# subliminal1.net
KiCad netlist of a schematic drawn in EAGLE
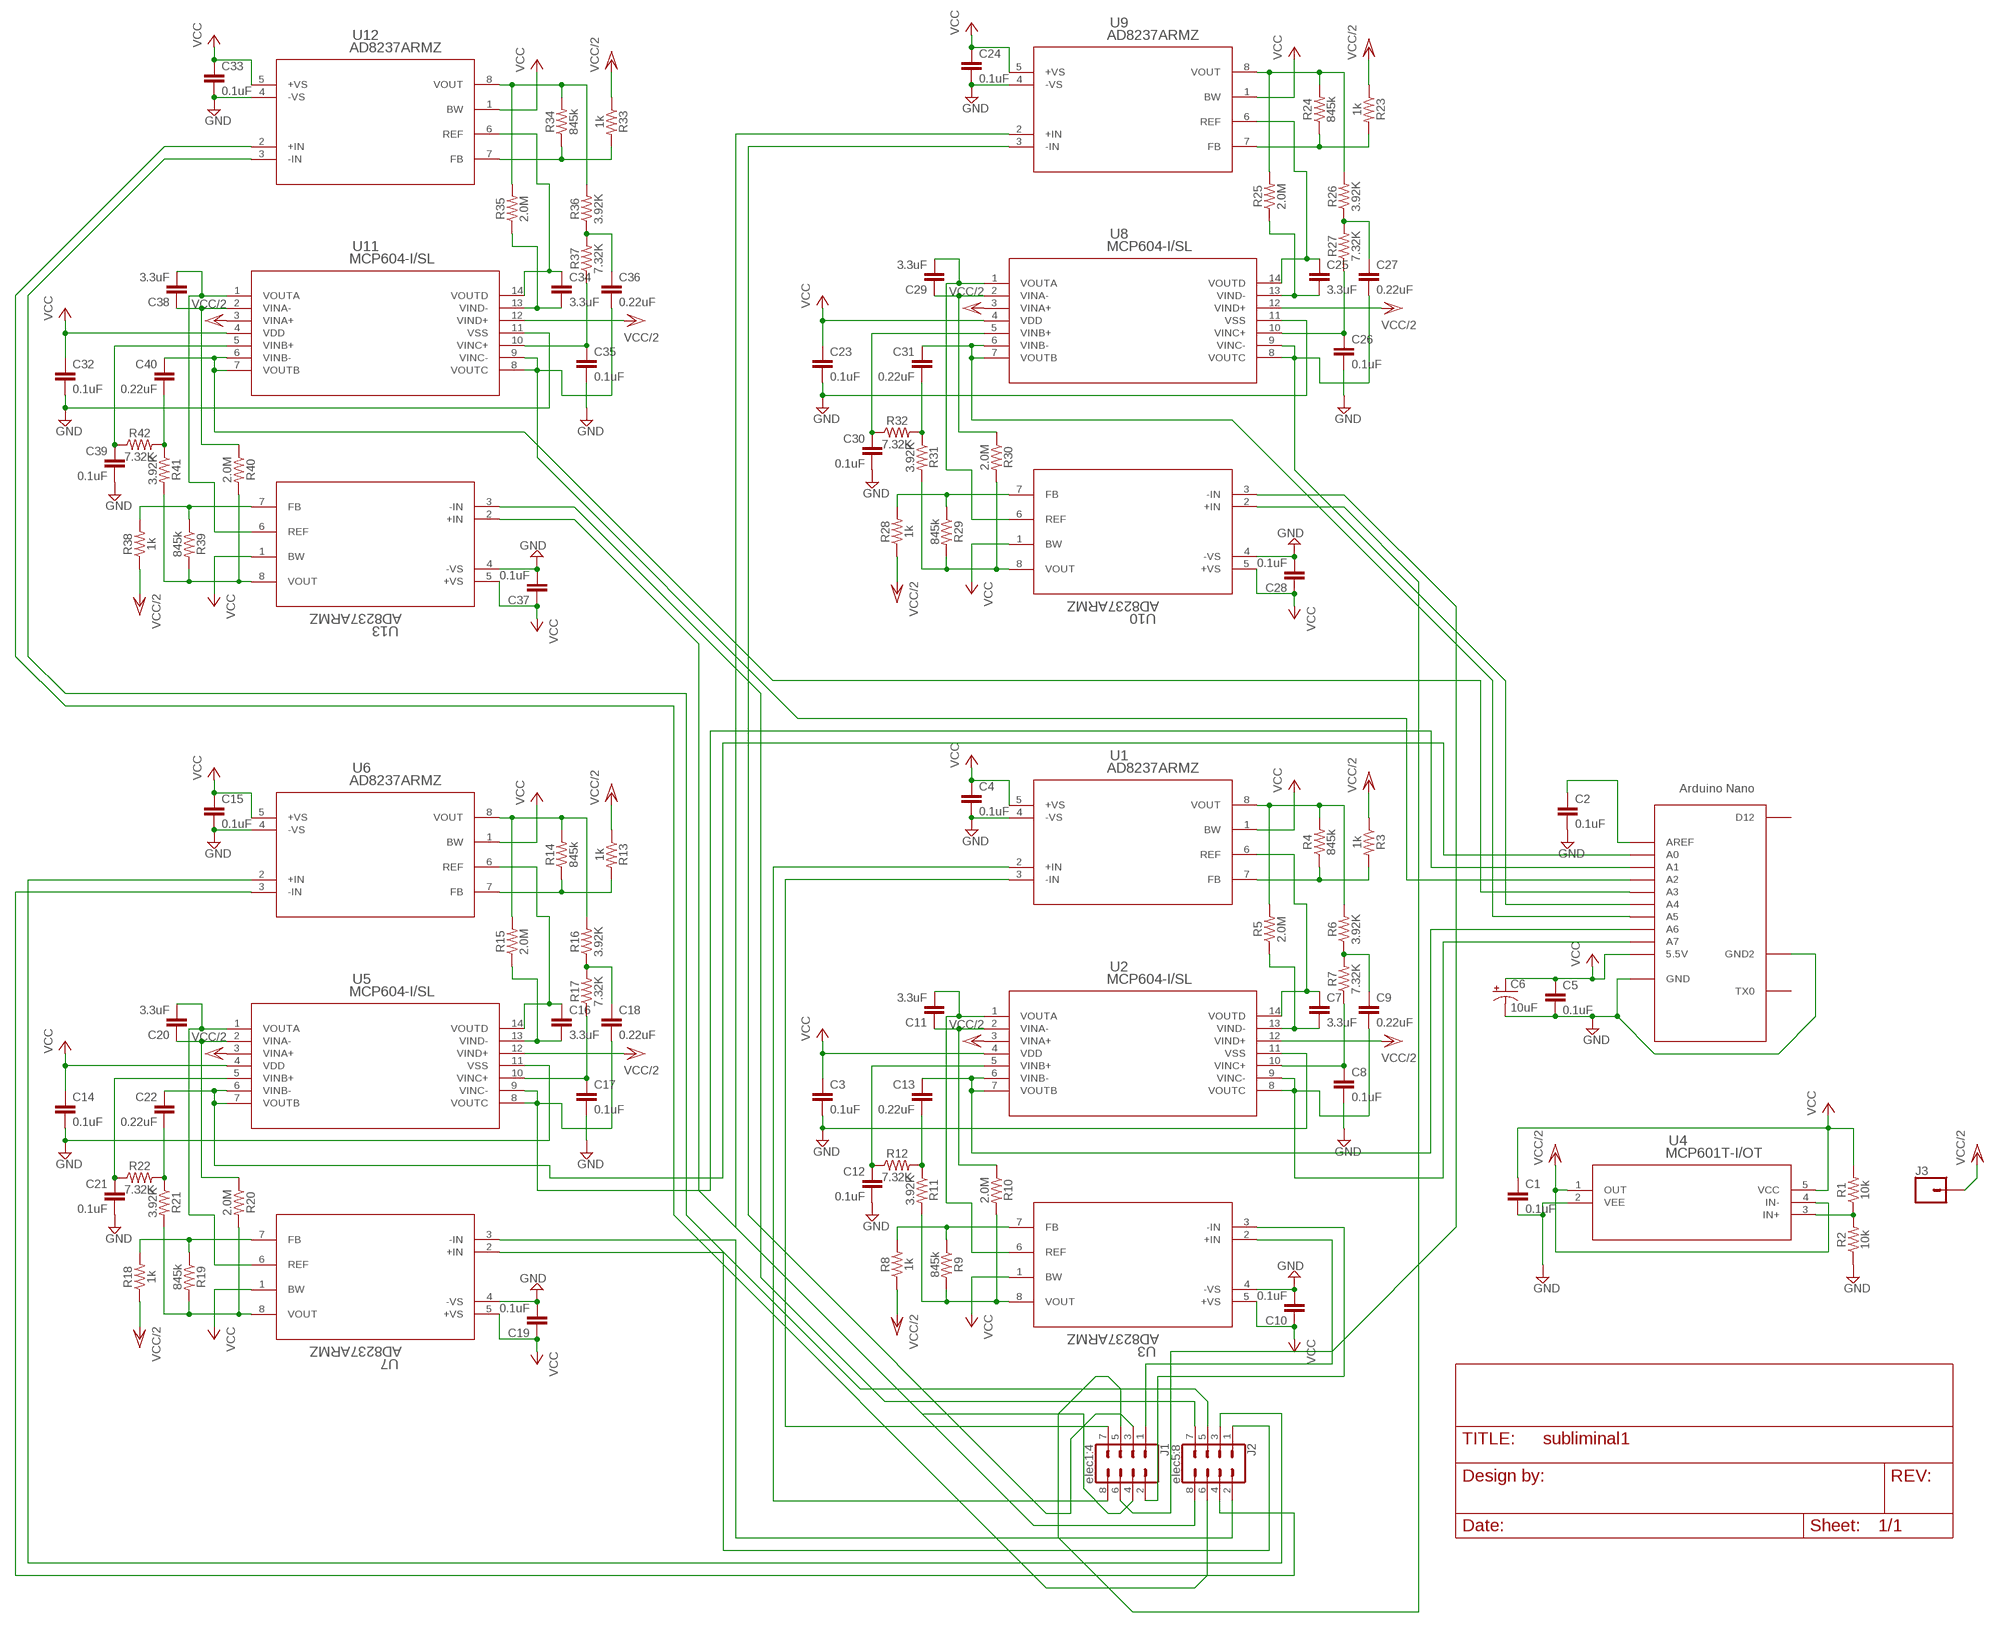
[diagram p0: schematic, sheet 1, part 1 of 2]
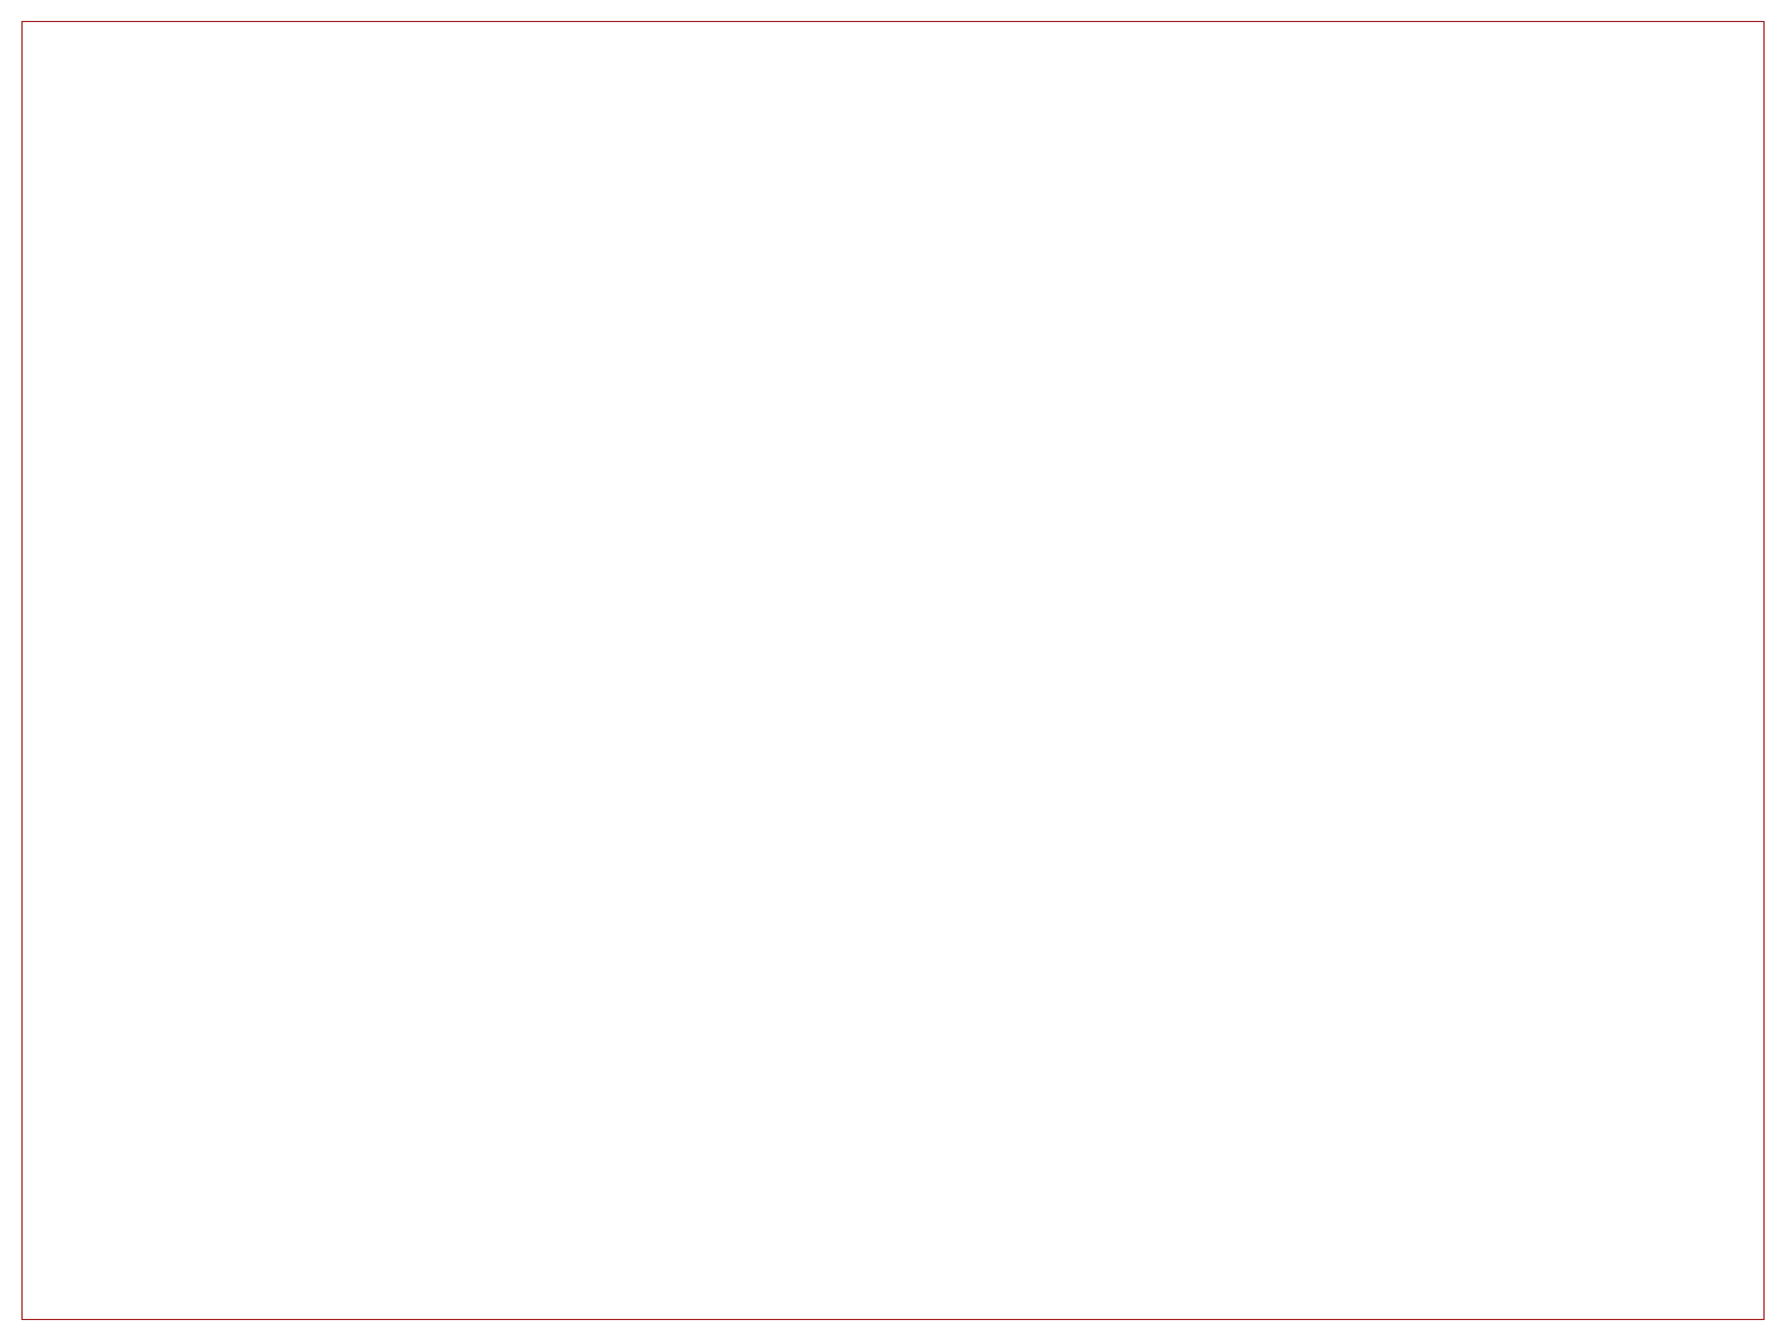
[diagram p1: schematic, sheet 1, part 2 of 2]

(export (version "E")
  (design (tool "Eeschema 10.0.6"))
  (components
    (comp (ref "C1")
      (value "0.1uF")
      (footprint "eagle-import:0603")
      (libsource (lib "eagle-import") (part "0.1UF-0603-25V-(+80/-20%)"))
    )
    (comp (ref "C2")
      (value "0.1uF")
      (footprint "eagle-import:0603")
      (libsource (lib "eagle-import") (part "0.1UF-0603-25V-(+80/-20%)"))
    )
    (comp (ref "C3")
      (value "0.1uF")
      (footprint "eagle-import:0603")
      (libsource (lib "eagle-import") (part "0.1UF-0603-25V-(+80/-20%)"))
    )
    (comp (ref "C4")
      (value "0.1uF")
      (footprint "eagle-import:0603")
      (libsource (lib "eagle-import") (part "0.1UF-0603-25V-(+80/-20%)"))
    )
    (comp (ref "C5")
      (value "0.1uF")
      (footprint "eagle-import:0603")
      (libsource (lib "eagle-import") (part "0.1UF-0603-25V-(+80/-20%)"))
    )
    (comp (ref "C6")
      (value "10uF")
      (footprint "eagle-import:EIA3216")
      (libsource (lib "eagle-import") (part "10UF-POLAR-EIA3216-16V-10%(TANT)"))
    )
    (comp (ref "C7")
      (value "3.3uF")
      (footprint "eagle-import:0603")
      (libsource (lib "eagle-import") (part "3.3UF-0603-10V-10%"))
    )
    (comp (ref "C8")
      (value "0.1uF")
      (footprint "eagle-import:0603")
      (libsource (lib "eagle-import") (part "0.1UF-0603-25V-(+80/-20%)"))
    )
    (comp (ref "C9")
      (value "0.22uF")
      (footprint "eagle-import:0603")
      (libsource (lib "eagle-import") (part "0.22UF-0603-25V-10%"))
    )
    (comp (ref "C10")
      (value "0.1uF")
      (footprint "eagle-import:0603")
      (libsource (lib "eagle-import") (part "0.1UF-0603-25V-(+80/-20%)"))
    )
    (comp (ref "C11")
      (value "3.3uF")
      (footprint "eagle-import:0603")
      (libsource (lib "eagle-import") (part "3.3UF-0603-10V-10%"))
    )
    (comp (ref "C12")
      (value "0.1uF")
      (footprint "eagle-import:0603")
      (libsource (lib "eagle-import") (part "0.1UF-0603-25V-(+80/-20%)"))
    )
    (comp (ref "C13")
      (value "0.22uF")
      (footprint "eagle-import:0603")
      (libsource (lib "eagle-import") (part "0.22UF-0603-25V-10%"))
    )
    (comp (ref "C14")
      (value "0.1uF")
      (footprint "eagle-import:0603")
      (libsource (lib "eagle-import") (part "0.1UF-0603-25V-(+80/-20%)"))
    )
    (comp (ref "C15")
      (value "0.1uF")
      (footprint "eagle-import:0603")
      (libsource (lib "eagle-import") (part "0.1UF-0603-25V-(+80/-20%)"))
    )
    (comp (ref "C16")
      (value "3.3uF")
      (footprint "eagle-import:0603")
      (libsource (lib "eagle-import") (part "3.3UF-0603-10V-10%"))
    )
    (comp (ref "C17")
      (value "0.1uF")
      (footprint "eagle-import:0603")
      (libsource (lib "eagle-import") (part "0.1UF-0603-25V-(+80/-20%)"))
    )
    (comp (ref "C18")
      (value "0.22uF")
      (footprint "eagle-import:0603")
      (libsource (lib "eagle-import") (part "0.22UF-0603-25V-10%"))
    )
    (comp (ref "C19")
      (value "0.1uF")
      (footprint "eagle-import:0603")
      (libsource (lib "eagle-import") (part "0.1UF-0603-25V-(+80/-20%)"))
    )
    (comp (ref "C20")
      (value "3.3uF")
      (footprint "eagle-import:0603")
      (libsource (lib "eagle-import") (part "3.3UF-0603-10V-10%"))
    )
    (comp (ref "C21")
      (value "0.1uF")
      (footprint "eagle-import:0603")
      (libsource (lib "eagle-import") (part "0.1UF-0603-25V-(+80/-20%)"))
    )
    (comp (ref "C22")
      (value "0.22uF")
      (footprint "eagle-import:0603")
      (libsource (lib "eagle-import") (part "0.22UF-0603-25V-10%"))
    )
    (comp (ref "C23")
      (value "0.1uF")
      (footprint "eagle-import:0603")
      (libsource (lib "eagle-import") (part "0.1UF-0603-25V-(+80/-20%)"))
    )
    (comp (ref "C24")
      (value "0.1uF")
      (footprint "eagle-import:0603")
      (libsource (lib "eagle-import") (part "0.1UF-0603-25V-(+80/-20%)"))
    )
    (comp (ref "C25")
      (value "3.3uF")
      (footprint "eagle-import:0603")
      (libsource (lib "eagle-import") (part "3.3UF-0603-10V-10%"))
    )
    (comp (ref "C26")
      (value "0.1uF")
      (footprint "eagle-import:0603")
      (libsource (lib "eagle-import") (part "0.1UF-0603-25V-(+80/-20%)"))
    )
    (comp (ref "C27")
      (value "0.22uF")
      (footprint "eagle-import:0603")
      (libsource (lib "eagle-import") (part "0.22UF-0603-25V-10%"))
    )
    (comp (ref "C28")
      (value "0.1uF")
      (footprint "eagle-import:0603")
      (libsource (lib "eagle-import") (part "0.1UF-0603-25V-(+80/-20%)"))
    )
    (comp (ref "C29")
      (value "3.3uF")
      (footprint "eagle-import:0603")
      (libsource (lib "eagle-import") (part "3.3UF-0603-10V-10%"))
    )
    (comp (ref "C30")
      (value "0.1uF")
      (footprint "eagle-import:0603")
      (libsource (lib "eagle-import") (part "0.1UF-0603-25V-(+80/-20%)"))
    )
    (comp (ref "C31")
      (value "0.22uF")
      (footprint "eagle-import:0603")
      (libsource (lib "eagle-import") (part "0.22UF-0603-25V-10%"))
    )
    (comp (ref "C32")
      (value "0.1uF")
      (footprint "eagle-import:0603")
      (libsource (lib "eagle-import") (part "0.1UF-0603-25V-(+80/-20%)"))
    )
    (comp (ref "C33")
      (value "0.1uF")
      (footprint "eagle-import:0603")
      (libsource (lib "eagle-import") (part "0.1UF-0603-25V-(+80/-20%)"))
    )
    (comp (ref "C34")
      (value "3.3uF")
      (footprint "eagle-import:0603")
      (libsource (lib "eagle-import") (part "3.3UF-0603-10V-10%"))
    )
    (comp (ref "C35")
      (value "0.1uF")
      (footprint "eagle-import:0603")
      (libsource (lib "eagle-import") (part "0.1UF-0603-25V-(+80/-20%)"))
    )
    (comp (ref "C36")
      (value "0.22uF")
      (footprint "eagle-import:0603")
      (libsource (lib "eagle-import") (part "0.22UF-0603-25V-10%"))
    )
    (comp (ref "C37")
      (value "0.1uF")
      (footprint "eagle-import:0603")
      (libsource (lib "eagle-import") (part "0.1UF-0603-25V-(+80/-20%)"))
    )
    (comp (ref "C38")
      (value "3.3uF")
      (footprint "eagle-import:0603")
      (libsource (lib "eagle-import") (part "3.3UF-0603-10V-10%"))
    )
    (comp (ref "C39")
      (value "0.1uF")
      (footprint "eagle-import:0603")
      (libsource (lib "eagle-import") (part "0.1UF-0603-25V-(+80/-20%)"))
    )
    (comp (ref "C40")
      (value "0.22uF")
      (footprint "eagle-import:0603")
      (libsource (lib "eagle-import") (part "0.22UF-0603-25V-10%"))
    )
    (comp (ref "J1")
      (value "elec1:4")
      (footprint "eagle-import:2X4")
      (libsource (lib "eagle-import") (part "CONN_04X2"))
    )
    (comp (ref "J2")
      (value "elec5:8")
      (footprint "eagle-import:2X4")
      (libsource (lib "eagle-import") (part "CONN_04X2"))
    )
    (comp (ref "J3")
      (value "CONN_01")
      (footprint "eagle-import:1X01")
      (libsource (lib "eagle-import") (part "CONN_01"))
    )
    (comp (ref "R1")
      (value "10k")
      (footprint "eagle-import:0603")
      (libsource (lib "eagle-import") (part "10KOHM-0603-1/10W-1%"))
    )
    (comp (ref "R2")
      (value "10k")
      (footprint "eagle-import:0603")
      (libsource (lib "eagle-import") (part "10KOHM-0603-1/10W-1%"))
    )
    (comp (ref "R3")
      (value "1k")
      (footprint "eagle-import:0603")
      (libsource (lib "eagle-import") (part "1KOHM-0603-1/10W-1%"))
    )
    (comp (ref "R4")
      (value "845k")
      (footprint "eagle-import:0603")
      (libsource (lib "eagle-import") (part "845KOHM-0603-1/10W-1%"))
    )
    (comp (ref "R5")
      (value "2.0M")
      (footprint "eagle-import:0603")
      (libsource (lib "eagle-import") (part "2MOHMS-0603-1/10W-1%"))
    )
    (comp (ref "R6")
      (value "3.92K")
      (footprint "eagle-import:0603")
      (libsource (lib "eagle-import") (part "3.92KOHM-0603-1/10W-1%"))
    )
    (comp (ref "R7")
      (value "7.32K")
      (footprint "eagle-import:0603")
      (libsource (lib "eagle-import") (part "7.32KOHM-0603-1/10W-1%"))
    )
    (comp (ref "R8")
      (value "1k")
      (footprint "eagle-import:0603")
      (libsource (lib "eagle-import") (part "1KOHM-0603-1/10W-1%"))
    )
    (comp (ref "R9")
      (value "845k")
      (footprint "eagle-import:0603")
      (libsource (lib "eagle-import") (part "845KOHM-0603-1/10W-1%"))
    )
    (comp (ref "R10")
      (value "2.0M")
      (footprint "eagle-import:0603")
      (libsource (lib "eagle-import") (part "2MOHMS-0603-1/10W-1%"))
    )
    (comp (ref "R11")
      (value "3.92K")
      (footprint "eagle-import:0603")
      (libsource (lib "eagle-import") (part "3.92KOHM-0603-1/10W-1%"))
    )
    (comp (ref "R12")
      (value "7.32K")
      (footprint "eagle-import:0603")
      (libsource (lib "eagle-import") (part "7.32KOHM-0603-1/10W-1%"))
    )
    (comp (ref "R13")
      (value "1k")
      (footprint "eagle-import:0603")
      (libsource (lib "eagle-import") (part "1KOHM-0603-1/10W-1%"))
    )
    (comp (ref "R14")
      (value "845k")
      (footprint "eagle-import:0603")
      (libsource (lib "eagle-import") (part "845KOHM-0603-1/10W-1%"))
    )
    (comp (ref "R15")
      (value "2.0M")
      (footprint "eagle-import:0603")
      (libsource (lib "eagle-import") (part "2MOHMS-0603-1/10W-1%"))
    )
    (comp (ref "R16")
      (value "3.92K")
      (footprint "eagle-import:0603")
      (libsource (lib "eagle-import") (part "3.92KOHM-0603-1/10W-1%"))
    )
    (comp (ref "R17")
      (value "7.32K")
      (footprint "eagle-import:0603")
      (libsource (lib "eagle-import") (part "7.32KOHM-0603-1/10W-1%"))
    )
    (comp (ref "R18")
      (value "1k")
      (footprint "eagle-import:0603")
      (libsource (lib "eagle-import") (part "1KOHM-0603-1/10W-1%"))
    )
    (comp (ref "R19")
      (value "845k")
      (footprint "eagle-import:0603")
      (libsource (lib "eagle-import") (part "845KOHM-0603-1/10W-1%"))
    )
    (comp (ref "R20")
      (value "2.0M")
      (footprint "eagle-import:0603")
      (libsource (lib "eagle-import") (part "2MOHMS-0603-1/10W-1%"))
    )
    (comp (ref "R21")
      (value "3.92K")
      (footprint "eagle-import:0603")
      (libsource (lib "eagle-import") (part "3.92KOHM-0603-1/10W-1%"))
    )
    (comp (ref "R22")
      (value "7.32K")
      (footprint "eagle-import:0603")
      (libsource (lib "eagle-import") (part "7.32KOHM-0603-1/10W-1%"))
    )
    (comp (ref "R23")
      (value "1k")
      (footprint "eagle-import:0603")
      (libsource (lib "eagle-import") (part "1KOHM-0603-1/10W-1%"))
    )
    (comp (ref "R24")
      (value "845k")
      (footprint "eagle-import:0603")
      (libsource (lib "eagle-import") (part "845KOHM-0603-1/10W-1%"))
    )
    (comp (ref "R25")
      (value "2.0M")
      (footprint "eagle-import:0603")
      (libsource (lib "eagle-import") (part "2MOHMS-0603-1/10W-1%"))
    )
    (comp (ref "R26")
      (value "3.92K")
      (footprint "eagle-import:0603")
      (libsource (lib "eagle-import") (part "3.92KOHM-0603-1/10W-1%"))
    )
    (comp (ref "R27")
      (value "7.32K")
      (footprint "eagle-import:0603")
      (libsource (lib "eagle-import") (part "7.32KOHM-0603-1/10W-1%"))
    )
    (comp (ref "R28")
      (value "1k")
      (footprint "eagle-import:0603")
      (libsource (lib "eagle-import") (part "1KOHM-0603-1/10W-1%"))
    )
    (comp (ref "R29")
      (value "845k")
      (footprint "eagle-import:0603")
      (libsource (lib "eagle-import") (part "845KOHM-0603-1/10W-1%"))
    )
    (comp (ref "R30")
      (value "2.0M")
      (footprint "eagle-import:0603")
      (libsource (lib "eagle-import") (part "2MOHMS-0603-1/10W-1%"))
    )
    (comp (ref "R31")
      (value "3.92K")
      (footprint "eagle-import:0603")
      (libsource (lib "eagle-import") (part "3.92KOHM-0603-1/10W-1%"))
    )
    (comp (ref "R32")
      (value "7.32K")
      (footprint "eagle-import:0603")
      (libsource (lib "eagle-import") (part "7.32KOHM-0603-1/10W-1%"))
    )
    (comp (ref "R33")
      (value "1k")
      (footprint "eagle-import:0603")
      (libsource (lib "eagle-import") (part "1KOHM-0603-1/10W-1%"))
    )
    (comp (ref "R34")
      (value "845k")
      (footprint "eagle-import:0603")
      (libsource (lib "eagle-import") (part "845KOHM-0603-1/10W-1%"))
    )
    (comp (ref "R35")
      (value "2.0M")
      (footprint "eagle-import:0603")
      (libsource (lib "eagle-import") (part "2MOHMS-0603-1/10W-1%"))
    )
    (comp (ref "R36")
      (value "3.92K")
      (footprint "eagle-import:0603")
      (libsource (lib "eagle-import") (part "3.92KOHM-0603-1/10W-1%"))
    )
    (comp (ref "R37")
      (value "7.32K")
      (footprint "eagle-import:0603")
      (libsource (lib "eagle-import") (part "7.32KOHM-0603-1/10W-1%"))
    )
    (comp (ref "R38")
      (value "1k")
      (footprint "eagle-import:0603")
      (libsource (lib "eagle-import") (part "1KOHM-0603-1/10W-1%"))
    )
    (comp (ref "R39")
      (value "845k")
      (footprint "eagle-import:0603")
      (libsource (lib "eagle-import") (part "845KOHM-0603-1/10W-1%"))
    )
    (comp (ref "R40")
      (value "2.0M")
      (footprint "eagle-import:0603")
      (libsource (lib "eagle-import") (part "2MOHMS-0603-1/10W-1%"))
    )
    (comp (ref "R41")
      (value "3.92K")
      (footprint "eagle-import:0603")
      (libsource (lib "eagle-import") (part "3.92KOHM-0603-1/10W-1%"))
    )
    (comp (ref "R42")
      (value "7.32K")
      (footprint "eagle-import:0603")
      (libsource (lib "eagle-import") (part "7.32KOHM-0603-1/10W-1%"))
    )
    (comp (ref "U$1")
      (value "ANALOG-NANO")
      (footprint "eagle-import:ANANANOMIN")
      (libsource (lib "eagle-import") (part "ANALOG-NANO"))
    )
    (comp (ref "U1")
      (value "AD8237ARMZ")
      (footprint "eagle-import:RM_8")
      (libsource (lib "eagle-import") (part "AD8237ARMZ"))
    )
    (comp (ref "U2")
      (value "MCP604-I/SL")
      (footprint "eagle-import:SOIC14-N_MC")
      (fields (field (name "MANUFACTURER_PART_NUMBER") "MCP604ISL"))
      (libsource (lib "eagle-import") (part "MCP604-I/SL"))
    )
    (comp (ref "U3")
      (value "AD8237ARMZ")
      (footprint "eagle-import:RM_8")
      (libsource (lib "eagle-import") (part "AD8237ARMZ"))
    )
    (comp (ref "U4")
      (value "MCP601T-I/OT")
      (footprint "eagle-import:SOT-23-5_MC")
      (fields (field (name "MANUFACTURER_PART_NUMBER") "MCP601TIOT"))
      (libsource (lib "eagle-import") (part "MCP601T-I/OT"))
    )
    (comp (ref "U5")
      (value "MCP604-I/SL")
      (footprint "eagle-import:SOIC14-N_MC")
      (fields (field (name "MANUFACTURER_PART_NUMBER") "MCP604ISL"))
      (libsource (lib "eagle-import") (part "MCP604-I/SL"))
    )
    (comp (ref "U6")
      (value "AD8237ARMZ")
      (footprint "eagle-import:RM_8")
      (libsource (lib "eagle-import") (part "AD8237ARMZ"))
    )
    (comp (ref "U7")
      (value "AD8237ARMZ")
      (footprint "eagle-import:RM_8")
      (libsource (lib "eagle-import") (part "AD8237ARMZ"))
    )
    (comp (ref "U8")
      (value "MCP604-I/SL")
      (footprint "eagle-import:SOIC14-N_MC")
      (fields (field (name "MANUFACTURER_PART_NUMBER") "MCP604ISL"))
      (libsource (lib "eagle-import") (part "MCP604-I/SL"))
    )
    (comp (ref "U9")
      (value "AD8237ARMZ")
      (footprint "eagle-import:RM_8")
      (libsource (lib "eagle-import") (part "AD8237ARMZ"))
    )
    (comp (ref "U10")
      (value "AD8237ARMZ")
      (footprint "eagle-import:RM_8")
      (libsource (lib "eagle-import") (part "AD8237ARMZ"))
    )
    (comp (ref "U11")
      (value "MCP604-I/SL")
      (footprint "eagle-import:SOIC14-N_MC")
      (fields (field (name "MANUFACTURER_PART_NUMBER") "MCP604ISL"))
      (libsource (lib "eagle-import") (part "MCP604-I/SL"))
    )
    (comp (ref "U12")
      (value "AD8237ARMZ")
      (footprint "eagle-import:RM_8")
      (libsource (lib "eagle-import") (part "AD8237ARMZ"))
    )
    (comp (ref "U13")
      (value "AD8237ARMZ")
      (footprint "eagle-import:RM_8")
      (libsource (lib "eagle-import") (part "AD8237ARMZ"))
    )
  )
  (nets
    (net (code "1") (name "GND") (class "Default")
      (node (ref "C1") (pin "2") (pinfunction "2_2") (pintype "passive"))
      (node (ref "C10") (pin "2") (pinfunction "2_2") (pintype "passive"))
      (node (ref "C12") (pin "2") (pinfunction "2_2") (pintype "passive"))
      (node (ref "C14") (pin "2") (pinfunction "2_2") (pintype "passive"))
      (node (ref "C15") (pin "2") (pinfunction "2_2") (pintype "passive"))
      (node (ref "C17") (pin "2") (pinfunction "2_2") (pintype "passive"))
      (node (ref "C19") (pin "2") (pinfunction "2_2") (pintype "passive"))
      (node (ref "C2") (pin "2") (pinfunction "2_2") (pintype "passive"))
      (node (ref "C21") (pin "2") (pinfunction "2_2") (pintype "passive"))
      (node (ref "C23") (pin "2") (pinfunction "2_2") (pintype "passive"))
      (node (ref "C24") (pin "2") (pinfunction "2_2") (pintype "passive"))
      (node (ref "C26") (pin "2") (pinfunction "2_2") (pintype "passive"))
      (node (ref "C28") (pin "2") (pinfunction "2_2") (pintype "passive"))
      (node (ref "C3") (pin "2") (pinfunction "2_2") (pintype "passive"))
      (node (ref "C30") (pin "2") (pinfunction "2_2") (pintype "passive"))
      (node (ref "C32") (pin "2") (pinfunction "2_2") (pintype "passive"))
      (node (ref "C33") (pin "2") (pinfunction "2_2") (pintype "passive"))
      (node (ref "C35") (pin "2") (pinfunction "2_2") (pintype "passive"))
      (node (ref "C37") (pin "2") (pinfunction "2_2") (pintype "passive"))
      (node (ref "C39") (pin "2") (pinfunction "2_2") (pintype "passive"))
      (node (ref "C4") (pin "2") (pinfunction "2_2") (pintype "passive"))
      (node (ref "C5") (pin "2") (pinfunction "2_2") (pintype "passive"))
      (node (ref "C6") (pin "-") (pinfunction "-_-") (pintype "passive"))
      (node (ref "C8") (pin "2") (pinfunction "2_2") (pintype "passive"))
      (node (ref "R2") (pin "1") (pinfunction "1_1") (pintype "passive"))
      (node (ref "U$1") (pin "GND") (pinfunction "GND_GND") (pintype "bidirectional"))
      (node (ref "U$1") (pin "GND1") (pinfunction "GND2_GND1") (pintype "bidirectional"))
      (node (ref "U1") (pin "4") (pinfunction "-VS_4") (pintype "passive"))
      (node (ref "U10") (pin "4") (pinfunction "-VS_4") (pintype "passive"))
      (node (ref "U11") (pin "11") (pinfunction "VSS_11") (pintype "passive"))
      (node (ref "U12") (pin "4") (pinfunction "-VS_4") (pintype "passive"))
      (node (ref "U13") (pin "4") (pinfunction "-VS_4") (pintype "passive"))
      (node (ref "U2") (pin "11") (pinfunction "VSS_11") (pintype "passive"))
      (node (ref "U3") (pin "4") (pinfunction "-VS_4") (pintype "passive"))
      (node (ref "U4") (pin "2") (pinfunction "VEE_2") (pintype "passive"))
      (node (ref "U5") (pin "11") (pinfunction "VSS_11") (pintype "passive"))
      (node (ref "U6") (pin "4") (pinfunction "-VS_4") (pintype "passive"))
      (node (ref "U7") (pin "4") (pinfunction "-VS_4") (pintype "passive"))
      (node (ref "U8") (pin "11") (pinfunction "VSS_11") (pintype "passive"))
      (node (ref "U9") (pin "4") (pinfunction "-VS_4") (pintype "passive"))
    )
    (net (code "2") (name "Net-(C2-Pad1)") (class "Default")
      (node (ref "C2") (pin "1") (pinfunction "1_1") (pintype "passive"))
      (node (ref "U$1") (pin "AREF") (pinfunction "AREF_AREF") (pintype "bidirectional"))
    )
    (net (code "3") (name "Net-(C9-Pad1)") (class "Default")
      (node (ref "C9") (pin "1") (pinfunction "1_1") (pintype "passive"))
      (node (ref "R6") (pin "1") (pinfunction "1_1") (pintype "passive"))
      (node (ref "R7") (pin "2") (pinfunction "2_2") (pintype "passive"))
    )
    (net (code "4") (name "Net-(C13-Pad2)") (class "Default")
      (node (ref "C13") (pin "2") (pinfunction "2_2") (pintype "passive"))
      (node (ref "R11") (pin "1") (pinfunction "1_1") (pintype "passive"))
      (node (ref "R12") (pin "2") (pinfunction "2_2") (pintype "passive"))
    )
    (net (code "5") (name "Net-(C18-Pad1)") (class "Default")
      (node (ref "C18") (pin "1") (pinfunction "1_1") (pintype "passive"))
      (node (ref "R16") (pin "1") (pinfunction "1_1") (pintype "passive"))
      (node (ref "R17") (pin "2") (pinfunction "2_2") (pintype "passive"))
    )
    (net (code "6") (name "Net-(C22-Pad2)") (class "Default")
      (node (ref "C22") (pin "2") (pinfunction "2_2") (pintype "passive"))
      (node (ref "R21") (pin "1") (pinfunction "1_1") (pintype "passive"))
      (node (ref "R22") (pin "2") (pinfunction "2_2") (pintype "passive"))
    )
    (net (code "7") (name "Net-(C27-Pad1)") (class "Default")
      (node (ref "C27") (pin "1") (pinfunction "1_1") (pintype "passive"))
      (node (ref "R26") (pin "1") (pinfunction "1_1") (pintype "passive"))
      (node (ref "R27") (pin "2") (pinfunction "2_2") (pintype "passive"))
    )
    (net (code "8") (name "Net-(C31-Pad2)") (class "Default")
      (node (ref "C31") (pin "2") (pinfunction "2_2") (pintype "passive"))
      (node (ref "R31") (pin "1") (pinfunction "1_1") (pintype "passive"))
      (node (ref "R32") (pin "2") (pinfunction "2_2") (pintype "passive"))
    )
    (net (code "9") (name "Net-(C36-Pad1)") (class "Default")
      (node (ref "C36") (pin "1") (pinfunction "1_1") (pintype "passive"))
      (node (ref "R36") (pin "1") (pinfunction "1_1") (pintype "passive"))
      (node (ref "R37") (pin "2") (pinfunction "2_2") (pintype "passive"))
    )
    (net (code "10") (name "Net-(C40-Pad2)") (class "Default")
      (node (ref "C40") (pin "2") (pinfunction "2_2") (pintype "passive"))
      (node (ref "R41") (pin "1") (pinfunction "1_1") (pintype "passive"))
      (node (ref "R42") (pin "2") (pinfunction "2_2") (pintype "passive"))
    )
    (net (code "11") (name "Net-(U1-+IN)") (class "Default")
      (node (ref "J1") (pin "8") (pinfunction "8_8") (pintype "passive"))
      (node (ref "U1") (pin "2") (pinfunction "+IN_2") (pintype "passive"))
    )
    (net (code "12") (name "Net-(U1--IN)") (class "Default")
      (node (ref "J1") (pin "7") (pinfunction "7_7") (pintype "passive"))
      (node (ref "U1") (pin "3") (pinfunction "-IN_3") (pintype "passive"))
    )
    (net (code "13") (name "Net-(U1-FB)") (class "Default")
      (node (ref "R3") (pin "2") (pinfunction "2_2") (pintype "passive"))
      (node (ref "R4") (pin "1") (pinfunction "1_1") (pintype "passive"))
      (node (ref "U1") (pin "7") (pinfunction "FB_7") (pintype "passive"))
    )
    (net (code "14") (name "Net-(U1-REF)") (class "Default")
      (node (ref "C7") (pin "1") (pinfunction "1_1") (pintype "passive"))
      (node (ref "U1") (pin "6") (pinfunction "REF_6") (pintype "passive"))
      (node (ref "U2") (pin "14") (pinfunction "VOUTD_14") (pintype "output"))
    )
    (net (code "15") (name "Net-(U1-VOUT)") (class "Default")
      (node (ref "R4") (pin "2") (pinfunction "2_2") (pintype "passive"))
      (node (ref "R5") (pin "2") (pinfunction "2_2") (pintype "passive"))
      (node (ref "R6") (pin "2") (pinfunction "2_2") (pintype "passive"))
      (node (ref "U1") (pin "8") (pinfunction "VOUT_8") (pintype "passive"))
    )
    (net (code "16") (name "Net-(U2-VINA-)") (class "Default")
      (node (ref "C11") (pin "1") (pinfunction "1_1") (pintype "passive"))
      (node (ref "R10") (pin "1") (pinfunction "1_1") (pintype "passive"))
      (node (ref "U2") (pin "2") (pinfunction "VINA-_2") (pintype "input"))
    )
    (net (code "17") (name "Net-(U2-VINB+)") (class "Default")
      (node (ref "C12") (pin "1") (pinfunction "1_1") (pintype "passive"))
      (node (ref "R12") (pin "1") (pinfunction "1_1") (pintype "passive"))
      (node (ref "U2") (pin "5") (pinfunction "VINB+_5") (pintype "input"))
    )
    (net (code "18") (name "Net-(U2-VINB-)") (class "Default")
      (node (ref "C13") (pin "1") (pinfunction "1_1") (pintype "passive"))
      (node (ref "U$1") (pin "A6") (pinfunction "A6_A6") (pintype "bidirectional"))
      (node (ref "U2") (pin "6") (pinfunction "VINB-_6") (pintype "input"))
      (node (ref "U2") (pin "7") (pinfunction "VOUTB_7") (pintype "output"))
    )
    (net (code "19") (name "Net-(U2-VINC+)") (class "Default")
      (node (ref "C8") (pin "1") (pinfunction "1_1") (pintype "passive"))
      (node (ref "R7") (pin "1") (pinfunction "1_1") (pintype "passive"))
      (node (ref "U2") (pin "10") (pinfunction "VINC+_10") (pintype "input"))
    )
    (net (code "20") (name "Net-(U2-VINC-)") (class "Default")
      (node (ref "C9") (pin "2") (pinfunction "2_2") (pintype "passive"))
      (node (ref "U$1") (pin "A7") (pinfunction "A7_A7") (pintype "bidirectional"))
      (node (ref "U2") (pin "8") (pinfunction "VOUTC_8") (pintype "output"))
      (node (ref "U2") (pin "9") (pinfunction "VINC-_9") (pintype "input"))
    )
    (net (code "21") (name "Net-(U2-VIND-)") (class "Default")
      (node (ref "C7") (pin "2") (pinfunction "2_2") (pintype "passive"))
      (node (ref "R5") (pin "1") (pinfunction "1_1") (pintype "passive"))
      (node (ref "U2") (pin "13") (pinfunction "VIND-_13") (pintype "input"))
    )
    (net (code "22") (name "Net-(U2-VOUTA)") (class "Default")
      (node (ref "C11") (pin "2") (pinfunction "2_2") (pintype "passive"))
      (node (ref "U2") (pin "1") (pinfunction "VOUTA_1") (pintype "output"))
      (node (ref "U3") (pin "6") (pinfunction "REF_6") (pintype "passive"))
    )
    (net (code "23") (name "Net-(U3-+IN)") (class "Default")
      (node (ref "J1") (pin "1") (pinfunction "1_1") (pintype "passive"))
      (node (ref "U3") (pin "2") (pinfunction "+IN_2") (pintype "passive"))
    )
    (net (code "24") (name "Net-(U3--IN)") (class "Default")
      (node (ref "J1") (pin "2") (pinfunction "2_2") (pintype "passive"))
      (node (ref "U3") (pin "3") (pinfunction "-IN_3") (pintype "passive"))
    )
    (net (code "25") (name "Net-(U3-FB)") (class "Default")
      (node (ref "R8") (pin "2") (pinfunction "2_2") (pintype "passive"))
      (node (ref "R9") (pin "1") (pinfunction "1_1") (pintype "passive"))
      (node (ref "U3") (pin "7") (pinfunction "FB_7") (pintype "passive"))
    )
    (net (code "26") (name "Net-(U3-VOUT)") (class "Default")
      (node (ref "R10") (pin "2") (pinfunction "2_2") (pintype "passive"))
      (node (ref "R11") (pin "2") (pinfunction "2_2") (pintype "passive"))
      (node (ref "R9") (pin "2") (pinfunction "2_2") (pintype "passive"))
      (node (ref "U3") (pin "8") (pinfunction "VOUT_8") (pintype "passive"))
    )
    (net (code "27") (name "Net-(U4-IN+)") (class "Default")
      (node (ref "R1") (pin "1") (pinfunction "1_1") (pintype "passive"))
      (node (ref "R2") (pin "2") (pinfunction "2_2") (pintype "passive"))
      (node (ref "U4") (pin "3") (pinfunction "IN+_3") (pintype "passive"))
    )
    (net (code "28") (name "Net-(U5-VINA-)") (class "Default")
      (node (ref "C20") (pin "1") (pinfunction "1_1") (pintype "passive"))
      (node (ref "R20") (pin "1") (pinfunction "1_1") (pintype "passive"))
      (node (ref "U5") (pin "2") (pinfunction "VINA-_2") (pintype "input"))
    )
    (net (code "29") (name "Net-(U5-VINB+)") (class "Default")
      (node (ref "C21") (pin "1") (pinfunction "1_1") (pintype "passive"))
      (node (ref "R22") (pin "1") (pinfunction "1_1") (pintype "passive"))
      (node (ref "U5") (pin "5") (pinfunction "VINB+_5") (pintype "input"))
    )
    (net (code "30") (name "Net-(U5-VINB-)") (class "Default")
      (node (ref "C22") (pin "1") (pinfunction "1_1") (pintype "passive"))
      (node (ref "U$1") (pin "A0") (pinfunction "A0_A0") (pintype "bidirectional"))
      (node (ref "U5") (pin "6") (pinfunction "VINB-_6") (pintype "input"))
      (node (ref "U5") (pin "7") (pinfunction "VOUTB_7") (pintype "output"))
    )
    (net (code "31") (name "Net-(U5-VINC+)") (class "Default")
      (node (ref "C17") (pin "1") (pinfunction "1_1") (pintype "passive"))
      (node (ref "R17") (pin "1") (pinfunction "1_1") (pintype "passive"))
      (node (ref "U5") (pin "10") (pinfunction "VINC+_10") (pintype "input"))
    )
    (net (code "32") (name "Net-(U5-VINC-)") (class "Default")
      (node (ref "C18") (pin "2") (pinfunction "2_2") (pintype "passive"))
      (node (ref "U$1") (pin "A1") (pinfunction "A1_A1") (pintype "bidirectional"))
      (node (ref "U5") (pin "8") (pinfunction "VOUTC_8") (pintype "output"))
      (node (ref "U5") (pin "9") (pinfunction "VINC-_9") (pintype "input"))
    )
    (net (code "33") (name "Net-(U5-VIND-)") (class "Default")
      (node (ref "C16") (pin "2") (pinfunction "2_2") (pintype "passive"))
      (node (ref "R15") (pin "1") (pinfunction "1_1") (pintype "passive"))
      (node (ref "U5") (pin "13") (pinfunction "VIND-_13") (pintype "input"))
    )
    (net (code "34") (name "Net-(U5-VOUTA)") (class "Default")
      (node (ref "C20") (pin "2") (pinfunction "2_2") (pintype "passive"))
      (node (ref "U5") (pin "1") (pinfunction "VOUTA_1") (pintype "output"))
      (node (ref "U7") (pin "6") (pinfunction "REF_6") (pintype "passive"))
    )
    (net (code "35") (name "Net-(U5-VOUTD)") (class "Default")
      (node (ref "C16") (pin "1") (pinfunction "1_1") (pintype "passive"))
      (node (ref "U5") (pin "14") (pinfunction "VOUTD_14") (pintype "output"))
      (node (ref "U6") (pin "6") (pinfunction "REF_6") (pintype "passive"))
    )
    (net (code "36") (name "Net-(U6-+IN)") (class "Default")
      (node (ref "J2") (pin "3") (pinfunction "3_3") (pintype "passive"))
      (node (ref "U6") (pin "2") (pinfunction "+IN_2") (pintype "passive"))
    )
    (net (code "37") (name "Net-(U6--IN)") (class "Default")
      (node (ref "J2") (pin "4") (pinfunction "4_4") (pintype "passive"))
      (node (ref "U6") (pin "3") (pinfunction "-IN_3") (pintype "passive"))
    )
    (net (code "38") (name "Net-(U6-FB)") (class "Default")
      (node (ref "R13") (pin "2") (pinfunction "2_2") (pintype "passive"))
      (node (ref "R14") (pin "1") (pinfunction "1_1") (pintype "passive"))
      (node (ref "U6") (pin "7") (pinfunction "FB_7") (pintype "passive"))
    )
    (net (code "39") (name "Net-(U6-VOUT)") (class "Default")
      (node (ref "R14") (pin "2") (pinfunction "2_2") (pintype "passive"))
      (node (ref "R15") (pin "2") (pinfunction "2_2") (pintype "passive"))
      (node (ref "R16") (pin "2") (pinfunction "2_2") (pintype "passive"))
      (node (ref "U6") (pin "8") (pinfunction "VOUT_8") (pintype "passive"))
    )
    (net (code "40") (name "Net-(U7-+IN)") (class "Default")
      (node (ref "J2") (pin "1") (pinfunction "1_1") (pintype "passive"))
      (node (ref "U7") (pin "2") (pinfunction "+IN_2") (pintype "passive"))
    )
    (net (code "41") (name "Net-(U7--IN)") (class "Default")
      (node (ref "J2") (pin "2") (pinfunction "2_2") (pintype "passive"))
      (node (ref "U7") (pin "3") (pinfunction "-IN_3") (pintype "passive"))
    )
    (net (code "42") (name "Net-(U7-FB)") (class "Default")
      (node (ref "R18") (pin "2") (pinfunction "2_2") (pintype "passive"))
      (node (ref "R19") (pin "1") (pinfunction "1_1") (pintype "passive"))
      (node (ref "U7") (pin "7") (pinfunction "FB_7") (pintype "passive"))
    )
    (net (code "43") (name "Net-(U7-VOUT)") (class "Default")
      (node (ref "R19") (pin "2") (pinfunction "2_2") (pintype "passive"))
      (node (ref "R20") (pin "2") (pinfunction "2_2") (pintype "passive"))
      (node (ref "R21") (pin "2") (pinfunction "2_2") (pintype "passive"))
      (node (ref "U7") (pin "8") (pinfunction "VOUT_8") (pintype "passive"))
    )
    (net (code "44") (name "Net-(U8-VINA-)") (class "Default")
      (node (ref "C29") (pin "1") (pinfunction "1_1") (pintype "passive"))
      (node (ref "R30") (pin "1") (pinfunction "1_1") (pintype "passive"))
      (node (ref "U8") (pin "2") (pinfunction "VINA-_2") (pintype "input"))
    )
    (net (code "45") (name "Net-(U8-VINB+)") (class "Default")
      (node (ref "C30") (pin "1") (pinfunction "1_1") (pintype "passive"))
      (node (ref "R32") (pin "1") (pinfunction "1_1") (pintype "passive"))
      (node (ref "U8") (pin "5") (pinfunction "VINB+_5") (pintype "input"))
    )
    (net (code "46") (name "Net-(U8-VINB-)") (class "Default")
      (node (ref "C31") (pin "1") (pinfunction "1_1") (pintype "passive"))
      (node (ref "U$1") (pin "A5") (pinfunction "A5_A5") (pintype "bidirectional"))
      (node (ref "U8") (pin "6") (pinfunction "VINB-_6") (pintype "input"))
      (node (ref "U8") (pin "7") (pinfunction "VOUTB_7") (pintype "output"))
    )
    (net (code "47") (name "Net-(U8-VINC+)") (class "Default")
      (node (ref "C26") (pin "1") (pinfunction "1_1") (pintype "passive"))
      (node (ref "R27") (pin "1") (pinfunction "1_1") (pintype "passive"))
      (node (ref "U8") (pin "10") (pinfunction "VINC+_10") (pintype "input"))
    )
    (net (code "48") (name "Net-(U8-VINC-)") (class "Default")
      (node (ref "C27") (pin "2") (pinfunction "2_2") (pintype "passive"))
      (node (ref "U$1") (pin "A4") (pinfunction "A4_A4") (pintype "bidirectional"))
      (node (ref "U8") (pin "8") (pinfunction "VOUTC_8") (pintype "output"))
      (node (ref "U8") (pin "9") (pinfunction "VINC-_9") (pintype "input"))
    )
    (net (code "49") (name "Net-(U8-VIND-)") (class "Default")
      (node (ref "C25") (pin "2") (pinfunction "2_2") (pintype "passive"))
      (node (ref "R25") (pin "1") (pinfunction "1_1") (pintype "passive"))
      (node (ref "U8") (pin "13") (pinfunction "VIND-_13") (pintype "input"))
    )
    (net (code "50") (name "Net-(U8-VOUTD)") (class "Default")
      (node (ref "C25") (pin "1") (pinfunction "1_1") (pintype "passive"))
      (node (ref "U8") (pin "14") (pinfunction "VOUTD_14") (pintype "output"))
      (node (ref "U9") (pin "6") (pinfunction "REF_6") (pintype "passive"))
    )
    (net (code "51") (name "Net-(U9-+IN)") (class "Default")
      (node (ref "J1") (pin "4") (pinfunction "4_4") (pintype "passive"))
      (node (ref "U9") (pin "2") (pinfunction "+IN_2") (pintype "passive"))
    )
    (net (code "52") (name "Net-(U9--IN)") (class "Default")
      (node (ref "J1") (pin "3") (pinfunction "3_3") (pintype "passive"))
      (node (ref "U9") (pin "3") (pinfunction "-IN_3") (pintype "passive"))
    )
    (net (code "53") (name "Net-(U9-FB)") (class "Default")
      (node (ref "R23") (pin "2") (pinfunction "2_2") (pintype "passive"))
      (node (ref "R24") (pin "1") (pinfunction "1_1") (pintype "passive"))
      (node (ref "U9") (pin "7") (pinfunction "FB_7") (pintype "passive"))
    )
    (net (code "54") (name "Net-(U9-VOUT)") (class "Default")
      (node (ref "R24") (pin "2") (pinfunction "2_2") (pintype "passive"))
      (node (ref "R25") (pin "2") (pinfunction "2_2") (pintype "passive"))
      (node (ref "R26") (pin "2") (pinfunction "2_2") (pintype "passive"))
      (node (ref "U9") (pin "8") (pinfunction "VOUT_8") (pintype "passive"))
    )
    (net (code "55") (name "Net-(U10-+IN)") (class "Default")
      (node (ref "J1") (pin "5") (pinfunction "5_5") (pintype "passive"))
      (node (ref "U10") (pin "2") (pinfunction "+IN_2") (pintype "passive"))
    )
    (net (code "56") (name "Net-(U10--IN)") (class "Default")
      (node (ref "J1") (pin "6") (pinfunction "6_6") (pintype "passive"))
      (node (ref "U10") (pin "3") (pinfunction "-IN_3") (pintype "passive"))
    )
    (net (code "57") (name "Net-(U10-FB)") (class "Default")
      (node (ref "R28") (pin "2") (pinfunction "2_2") (pintype "passive"))
      (node (ref "R29") (pin "1") (pinfunction "1_1") (pintype "passive"))
      (node (ref "U10") (pin "7") (pinfunction "FB_7") (pintype "passive"))
    )
    (net (code "58") (name "Net-(U10-REF)") (class "Default")
      (node (ref "C29") (pin "2") (pinfunction "2_2") (pintype "passive"))
      (node (ref "U10") (pin "6") (pinfunction "REF_6") (pintype "passive"))
      (node (ref "U8") (pin "1") (pinfunction "VOUTA_1") (pintype "output"))
    )
    (net (code "59") (name "Net-(U10-VOUT)") (class "Default")
      (node (ref "R29") (pin "2") (pinfunction "2_2") (pintype "passive"))
      (node (ref "R30") (pin "2") (pinfunction "2_2") (pintype "passive"))
      (node (ref "R31") (pin "2") (pinfunction "2_2") (pintype "passive"))
      (node (ref "U10") (pin "8") (pinfunction "VOUT_8") (pintype "passive"))
    )
    (net (code "60") (name "Net-(U11-VINA-)") (class "Default")
      (node (ref "C38") (pin "1") (pinfunction "1_1") (pintype "passive"))
      (node (ref "R40") (pin "1") (pinfunction "1_1") (pintype "passive"))
      (node (ref "U11") (pin "2") (pinfunction "VINA-_2") (pintype "input"))
    )
    (net (code "61") (name "Net-(U11-VINB+)") (class "Default")
      (node (ref "C39") (pin "1") (pinfunction "1_1") (pintype "passive"))
      (node (ref "R42") (pin "1") (pinfunction "1_1") (pintype "passive"))
      (node (ref "U11") (pin "5") (pinfunction "VINB+_5") (pintype "input"))
    )
    (net (code "62") (name "Net-(U11-VINB-)") (class "Default")
      (node (ref "C40") (pin "1") (pinfunction "1_1") (pintype "passive"))
      (node (ref "U$1") (pin "A3") (pinfunction "A3_A3") (pintype "bidirectional"))
      (node (ref "U11") (pin "6") (pinfunction "VINB-_6") (pintype "input"))
      (node (ref "U11") (pin "7") (pinfunction "VOUTB_7") (pintype "output"))
    )
    (net (code "63") (name "Net-(U11-VINC+)") (class "Default")
      (node (ref "C35") (pin "1") (pinfunction "1_1") (pintype "passive"))
      (node (ref "R37") (pin "1") (pinfunction "1_1") (pintype "passive"))
      (node (ref "U11") (pin "10") (pinfunction "VINC+_10") (pintype "input"))
    )
    (net (code "64") (name "Net-(U11-VINC-)") (class "Default")
      (node (ref "C36") (pin "2") (pinfunction "2_2") (pintype "passive"))
      (node (ref "U$1") (pin "A2") (pinfunction "A2_A2") (pintype "bidirectional"))
      (node (ref "U11") (pin "8") (pinfunction "VOUTC_8") (pintype "output"))
      (node (ref "U11") (pin "9") (pinfunction "VINC-_9") (pintype "input"))
    )
    (net (code "65") (name "Net-(U11-VIND-)") (class "Default")
      (node (ref "C34") (pin "2") (pinfunction "2_2") (pintype "passive"))
      (node (ref "R35") (pin "1") (pinfunction "1_1") (pintype "passive"))
      (node (ref "U11") (pin "13") (pinfunction "VIND-_13") (pintype "input"))
    )
    (net (code "66") (name "Net-(U11-VOUTA)") (class "Default")
      (node (ref "C38") (pin "2") (pinfunction "2_2") (pintype "passive"))
      (node (ref "U11") (pin "1") (pinfunction "VOUTA_1") (pintype "output"))
      (node (ref "U13") (pin "6") (pinfunction "REF_6") (pintype "passive"))
    )
    (net (code "67") (name "Net-(U11-VOUTD)") (class "Default")
      (node (ref "C34") (pin "1") (pinfunction "1_1") (pintype "passive"))
      (node (ref "U11") (pin "14") (pinfunction "VOUTD_14") (pintype "output"))
      (node (ref "U12") (pin "6") (pinfunction "REF_6") (pintype "passive"))
    )
    (net (code "68") (name "Net-(U12-+IN)") (class "Default")
      (node (ref "J2") (pin "6") (pinfunction "6_6") (pintype "passive"))
      (node (ref "U12") (pin "2") (pinfunction "+IN_2") (pintype "passive"))
    )
    (net (code "69") (name "Net-(U12--IN)") (class "Default")
      (node (ref "J2") (pin "5") (pinfunction "5_5") (pintype "passive"))
      (node (ref "U12") (pin "3") (pinfunction "-IN_3") (pintype "passive"))
    )
    (net (code "70") (name "Net-(U12-FB)") (class "Default")
      (node (ref "R33") (pin "2") (pinfunction "2_2") (pintype "passive"))
      (node (ref "R34") (pin "1") (pinfunction "1_1") (pintype "passive"))
      (node (ref "U12") (pin "7") (pinfunction "FB_7") (pintype "passive"))
    )
    (net (code "71") (name "Net-(U12-VOUT)") (class "Default")
      (node (ref "R34") (pin "2") (pinfunction "2_2") (pintype "passive"))
      (node (ref "R35") (pin "2") (pinfunction "2_2") (pintype "passive"))
      (node (ref "R36") (pin "2") (pinfunction "2_2") (pintype "passive"))
      (node (ref "U12") (pin "8") (pinfunction "VOUT_8") (pintype "passive"))
    )
    (net (code "72") (name "Net-(U13-+IN)") (class "Default")
      (node (ref "J2") (pin "8") (pinfunction "8_8") (pintype "passive"))
      (node (ref "U13") (pin "2") (pinfunction "+IN_2") (pintype "passive"))
    )
    (net (code "73") (name "Net-(U13--IN)") (class "Default")
      (node (ref "J2") (pin "7") (pinfunction "7_7") (pintype "passive"))
      (node (ref "U13") (pin "3") (pinfunction "-IN_3") (pintype "passive"))
    )
    (net (code "74") (name "Net-(U13-FB)") (class "Default")
      (node (ref "R38") (pin "2") (pinfunction "2_2") (pintype "passive"))
      (node (ref "R39") (pin "1") (pinfunction "1_1") (pintype "passive"))
      (node (ref "U13") (pin "7") (pinfunction "FB_7") (pintype "passive"))
    )
    (net (code "75") (name "Net-(U13-VOUT)") (class "Default")
      (node (ref "R39") (pin "2") (pinfunction "2_2") (pintype "passive"))
      (node (ref "R40") (pin "2") (pinfunction "2_2") (pintype "passive"))
      (node (ref "R41") (pin "2") (pinfunction "2_2") (pintype "passive"))
      (node (ref "U13") (pin "8") (pinfunction "VOUT_8") (pintype "passive"))
    )
    (net (code "76") (name "VCC") (class "Default")
      (node (ref "C1") (pin "1") (pinfunction "1_1") (pintype "passive"))
      (node (ref "C10") (pin "1") (pinfunction "1_1") (pintype "passive"))
      (node (ref "C14") (pin "1") (pinfunction "1_1") (pintype "passive"))
      (node (ref "C15") (pin "1") (pinfunction "1_1") (pintype "passive"))
      (node (ref "C19") (pin "1") (pinfunction "1_1") (pintype "passive"))
      (node (ref "C23") (pin "1") (pinfunction "1_1") (pintype "passive"))
      (node (ref "C24") (pin "1") (pinfunction "1_1") (pintype "passive"))
      (node (ref "C28") (pin "1") (pinfunction "1_1") (pintype "passive"))
      (node (ref "C3") (pin "1") (pinfunction "1_1") (pintype "passive"))
      (node (ref "C32") (pin "1") (pinfunction "1_1") (pintype "passive"))
      (node (ref "C33") (pin "1") (pinfunction "1_1") (pintype "passive"))
      (node (ref "C37") (pin "1") (pinfunction "1_1") (pintype "passive"))
      (node (ref "C4") (pin "1") (pinfunction "1_1") (pintype "passive"))
      (node (ref "C5") (pin "1") (pinfunction "1_1") (pintype "passive"))
      (node (ref "C6") (pin "+") (pinfunction "+_+") (pintype "passive"))
      (node (ref "R1") (pin "2") (pinfunction "2_2") (pintype "passive"))
      (node (ref "U$1") (pin "5V") (pinfunction "5.5V_5V") (pintype "bidirectional"))
      (node (ref "U1") (pin "1") (pinfunction "BW_1") (pintype "passive"))
      (node (ref "U1") (pin "5") (pinfunction "+VS_5") (pintype "passive"))
      (node (ref "U10") (pin "1") (pinfunction "BW_1") (pintype "passive"))
      (node (ref "U10") (pin "5") (pinfunction "+VS_5") (pintype "passive"))
      (node (ref "U11") (pin "4") (pinfunction "VDD_4") (pintype "passive"))
      (node (ref "U12") (pin "1") (pinfunction "BW_1") (pintype "passive"))
      (node (ref "U12") (pin "5") (pinfunction "+VS_5") (pintype "passive"))
      (node (ref "U13") (pin "1") (pinfunction "BW_1") (pintype "passive"))
      (node (ref "U13") (pin "5") (pinfunction "+VS_5") (pintype "passive"))
      (node (ref "U2") (pin "4") (pinfunction "VDD_4") (pintype "passive"))
      (node (ref "U3") (pin "1") (pinfunction "BW_1") (pintype "passive"))
      (node (ref "U3") (pin "5") (pinfunction "+VS_5") (pintype "passive"))
      (node (ref "U4") (pin "5") (pinfunction "VCC_5") (pintype "passive"))
      (node (ref "U5") (pin "4") (pinfunction "VDD_4") (pintype "passive"))
      (node (ref "U6") (pin "1") (pinfunction "BW_1") (pintype "passive"))
      (node (ref "U6") (pin "5") (pinfunction "+VS_5") (pintype "passive"))
      (node (ref "U7") (pin "1") (pinfunction "BW_1") (pintype "passive"))
      (node (ref "U7") (pin "5") (pinfunction "+VS_5") (pintype "passive"))
      (node (ref "U8") (pin "4") (pinfunction "VDD_4") (pintype "passive"))
      (node (ref "U9") (pin "1") (pinfunction "BW_1") (pintype "passive"))
      (node (ref "U9") (pin "5") (pinfunction "+VS_5") (pintype "passive"))
    )
    (net (code "77") (name "VCC{slash}2") (class "Default")
      (node (ref "J3") (pin "1") (pinfunction "1_1") (pintype "passive"))
      (node (ref "R13") (pin "1") (pinfunction "1_1") (pintype "passive"))
      (node (ref "R18") (pin "1") (pinfunction "1_1") (pintype "passive"))
      (node (ref "R23") (pin "1") (pinfunction "1_1") (pintype "passive"))
      (node (ref "R28") (pin "1") (pinfunction "1_1") (pintype "passive"))
      (node (ref "R3") (pin "1") (pinfunction "1_1") (pintype "passive"))
      (node (ref "R33") (pin "1") (pinfunction "1_1") (pintype "passive"))
      (node (ref "R38") (pin "1") (pinfunction "1_1") (pintype "passive"))
      (node (ref "R8") (pin "1") (pinfunction "1_1") (pintype "passive"))
      (node (ref "U11") (pin "12") (pinfunction "VIND+_12") (pintype "input"))
      (node (ref "U11") (pin "3") (pinfunction "VINA+_3") (pintype "input"))
      (node (ref "U2") (pin "12") (pinfunction "VIND+_12") (pintype "input"))
      (node (ref "U2") (pin "3") (pinfunction "VINA+_3") (pintype "input"))
      (node (ref "U4") (pin "1") (pinfunction "OUT_1") (pintype "passive"))
      (node (ref "U4") (pin "4") (pinfunction "IN-_4") (pintype "passive"))
      (node (ref "U5") (pin "12") (pinfunction "VIND+_12") (pintype "input"))
      (node (ref "U5") (pin "3") (pinfunction "VINA+_3") (pintype "input"))
      (node (ref "U8") (pin "12") (pinfunction "VIND+_12") (pintype "input"))
      (node (ref "U8") (pin "3") (pinfunction "VINA+_3") (pintype "input"))
    )
    (net (code "78") (name "unconnected-(U$1-PadD12)") (class "Default")
      (node (ref "U$1") (pin "D12") (pinfunction "D12_D12") (pintype "bidirectional"))
    )
    (net (code "79") (name "unconnected-(U$1-PadTX0)") (class "Default")
      (node (ref "U$1") (pin "TX0") (pinfunction "TX0_TX0") (pintype "bidirectional"))
    )
  )
)
